# AMU-S23-V00-CURRENTPSU5V.net
KiCad netlist of a schematic drawn in Altium Designer
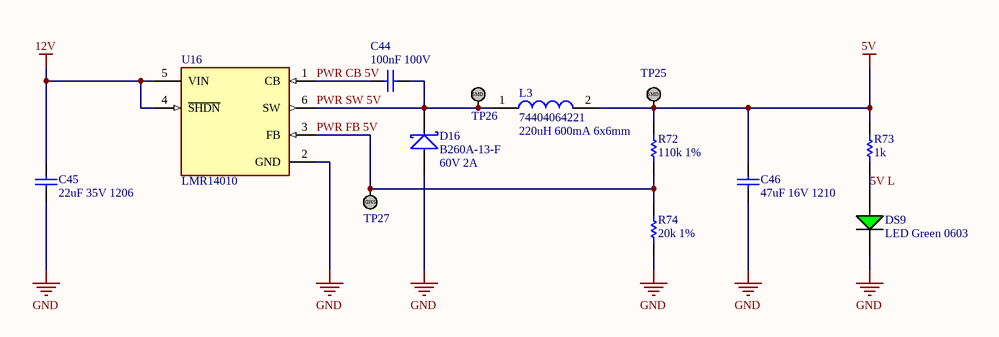
[diagram p0: AMU-S23-V00-CURRENTPSU5V.SchDoc]

(export (version "E")
  (design (tool "Eeschema 10.0.6"))
  (components
    (comp (ref "C44")
      (value "100nF 100V")
      (footprint "Cap_Ceramic_0603")
      (description "Capacitor, Ceramic, SMD, 100nF, 100V, 5%, X7R, 0603")
      (libsource (lib "StandardCapacitors") (part "100nF 100V 5% X7R 0603"))
    )
    (comp (ref "C45")
      (value "22uF 35V 1206")
      (footprint "Cap_Ceramic_1206")
      (description "Capacitor, Ceramic, SMD, 22uF, 35V, 10%, X7R, 1206")
      (libsource (lib "StandardCapacitors") (part "22uF 35V 10% X7R 1206"))
    )
    (comp (ref "C46")
      (value "47uF 16V 1210")
      (footprint "Cap_Ceramic_1210")
      (description "Capacitor, Ceramic, SMD, 47uF, 16V, 5%, X7R, 1210")
      (libsource (lib "StandardCapacitors") (part "47uF 16V 10% X7R 1210"))
    )
    (comp (ref "D16")
      (value "B260A-13-F")
      (footprint "SMA")
      (description "Diode, Schottky Barrier Rectifier, 60 V, 2 A, B260A-13-F")
      (libsource (lib "QUTMS_DiodeLibrary") (part "B260A-13-F"))
    )
    (comp (ref "DS9")
      (value "LED Green 0603")
      (footprint "LED GREEN 0603")
      (libsource (lib "QUTMS_LEDLibrary") (part "LED Green 0603"))
    )
    (comp (ref "L3")
      (value "74404064221")
      (footprint "Inductor_6x6mm")
      (description "FIXED IND 220UH 660MA 850 MOHM")
      (libsource (lib "QUTMS_InductorLibrary") (part "74404064221"))
    )
    (comp (ref "R72")
      (value "110k 1%")
      (footprint "Res_ThinFilm_0603")
      (description "Resistor, SMD, 111k, 0.1W, 1%, 0603")
      (libsource (lib "StandardResistors") (part "111k 1% 0603"))
    )
    (comp (ref "R73")
      (value "1k")
      (footprint "Res_ThinFilm_0603")
      (description "Resistor, SMD, 1k, 0.1W, 5%, 0603")
      (libsource (lib "StandardResistors") (part "1k 5% 0603"))
    )
    (comp (ref "R74")
      (value "20k 1%")
      (footprint "Res_ThinFilm_0603")
      (description "Resistor, SMD, 20k, 0.1W, 1%, 0603")
      (libsource (lib "StandardResistors") (part "20k 1% 0603"))
    )
    (comp (ref "TP25")
      (value "TestPoint_SMD")
      (footprint "TestPointSMD")
      (libsource (lib "StandardTest") (part "TestPoint_SMD"))
    )
    (comp (ref "TP26")
      (value "TestPoint_SMD")
      (footprint "TestPointSMD")
      (libsource (lib "StandardTest") (part "TestPoint_SMD"))
    )
    (comp (ref "TP27")
      (value "TestPoint_SMD")
      (footprint "TestPointSMD")
      (libsource (lib "StandardTest") (part "TestPoint_SMD"))
    )
    (comp (ref "U16")
      (value "LMR14010")
      (footprint "LMR14010")
      (libsource (lib "QUTMS_PowerSupplyLibrary") (part "LMR14010"))
    )
  )
  (nets
    (net (code "1") (name "/5V L") (class "Default")
      (node (ref "DS9") (pin "1") (pinfunction "A_1") (pintype "passive"))
      (node (ref "R73") (pin "1") (pinfunction "1_1") (pintype "passive"))
    )
    (net (code "2") (name "/PWR CB 5V") (class "Default")
      (node (ref "C44") (pin "1") (pinfunction "1_1") (pintype "passive"))
      (node (ref "U16") (pin "1") (pinfunction "CB_1") (pintype "input"))
    )
    (net (code "3") (name "/PWR FB 5V") (class "Default")
      (node (ref "R72") (pin "1") (pinfunction "1_1") (pintype "passive"))
      (node (ref "R74") (pin "2") (pinfunction "2_2") (pintype "passive"))
      (node (ref "TP27") (pin "1") (pinfunction "1_1") (pintype "passive"))
      (node (ref "U16") (pin "3") (pinfunction "FB_3") (pintype "input"))
    )
    (net (code "4") (name "/PWR SW 5V") (class "Default")
      (node (ref "C44") (pin "2") (pinfunction "2_2") (pintype "passive"))
      (node (ref "D16") (pin "K") (pinfunction "K_K") (pintype "passive"))
      (node (ref "L3") (pin "1") (pinfunction "1_1") (pintype "passive"))
      (node (ref "TP26") (pin "1") (pinfunction "1_1") (pintype "passive"))
      (node (ref "U16") (pin "6") (pinfunction "SW_6") (pintype "output"))
    )
    (net (code "5") (name "5V") (class "Default")
      (node (ref "C46") (pin "2") (pinfunction "2_2") (pintype "passive"))
      (node (ref "L3") (pin "2") (pinfunction "2_2") (pintype "passive"))
      (node (ref "R72") (pin "2") (pinfunction "2_2") (pintype "passive"))
      (node (ref "R73") (pin "2") (pinfunction "2_2") (pintype "passive"))
      (node (ref "TP25") (pin "1") (pinfunction "1_1") (pintype "passive"))
    )
    (net (code "6") (name "12V") (class "Default")
      (node (ref "C45") (pin "2") (pinfunction "2_2") (pintype "passive"))
      (node (ref "U16") (pin "4") (pinfunction "~{SHDN}_4") (pintype "input"))
      (node (ref "U16") (pin "5") (pinfunction "VIN_5") (pintype "power_in"))
    )
    (net (code "7") (name "GND") (class "Default")
      (node (ref "C45") (pin "1") (pinfunction "1_1") (pintype "passive"))
      (node (ref "C46") (pin "1") (pinfunction "1_1") (pintype "passive"))
      (node (ref "D16") (pin "A") (pinfunction "A_A") (pintype "passive"))
      (node (ref "DS9") (pin "2") (pinfunction "C_2") (pintype "passive"))
      (node (ref "R74") (pin "1") (pinfunction "1_1") (pintype "passive"))
      (node (ref "U16") (pin "2") (pinfunction "GND_2") (pintype "power_in"))
    )
  )
)
